# NAVIGATION_-_POWER.net
KiCad netlist of a schematic drawn in Altium Designer
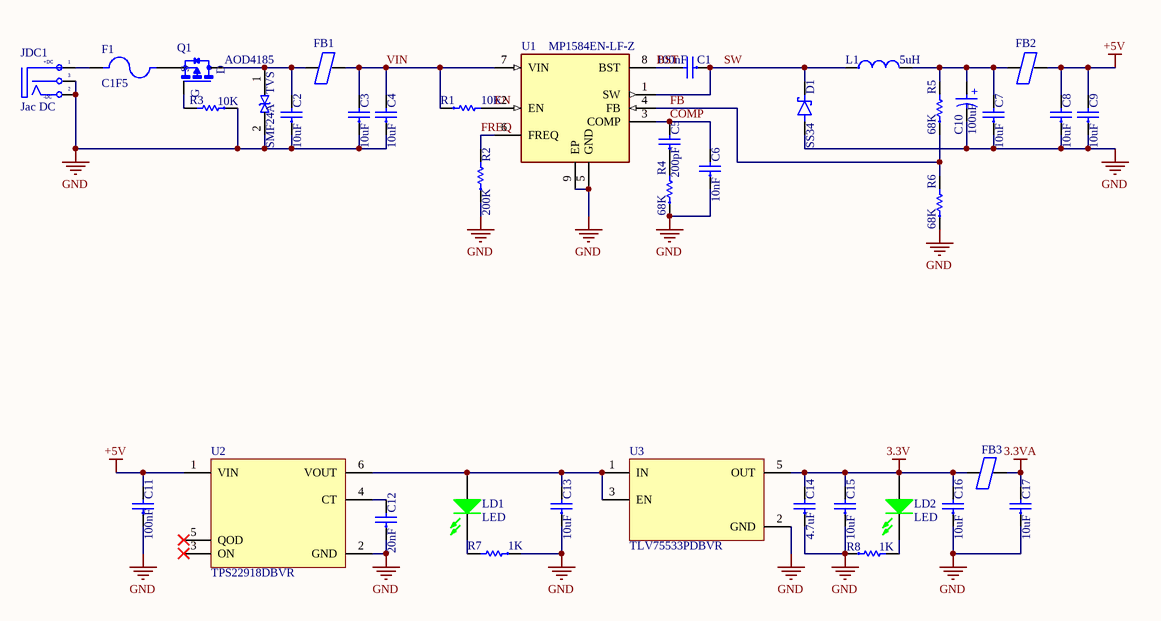
[diagram p0: NAVIGATION - POWER.SchDoc]

(export (version "E")
  (design (tool "Eeschema 10.0.6"))
  (components
    (comp (ref "C1")
      (value "100nF")
      (footprint "CAP-CER0402-0.5H")
      (description "CAP CER 100nF 10% 50V X7R 0402 SMD")
      (libsource (lib "2502-GMQLITE-MAIN") (part "CAPCER0013 100nF 10% 50V X7R 0402 SMD"))
    )
    (comp (ref "C2")
      (value "10uF")
      (footprint "CAP-CER0402-20mil")
      (description "CAP CER 10uF 20% 6.3V X5R 0402 SMD")
      (libsource (lib "2502-GMQLITE-MAIN") (part "CAPCER0040 10uF 20% 6.3V X5R 0402 SMD"))
    )
    (comp (ref "C3")
      (value "10uF")
      (footprint "CAP-CER0402-20mil")
      (description "CAP CER 10uF 20% 6.3V X5R 0402 SMD")
      (libsource (lib "2502-GMQLITE-MAIN") (part "CAPCER0040 10uF 20% 6.3V X5R 0402 SMD"))
    )
    (comp (ref "C4")
      (value "10uF")
      (footprint "CAP-CER0402-20mil")
      (description "CAP CER 10uF 20% 6.3V X5R 0402 SMD")
      (libsource (lib "2502-GMQLITE-MAIN") (part "CAPCER0040 10uF 20% 6.3V X5R 0402 SMD"))
    )
    (comp (ref "C5")
      (value "200pF")
      (footprint "CAP-CER0402-0.5H")
      (description "CAP CER 10nF 10% 25V X7R 0402 SMD")
      (libsource (lib "2502-GMQLITE-MAIN") (part "CAPCER0045 10nF 10% 25V X7R 0402 SMD"))
    )
    (comp (ref "C6")
      (value "10nF")
      (footprint "CAP-CER0402-0.5H")
      (description "CAP CER 10nF 10% 25V X7R 0402 SMD")
      (libsource (lib "2502-GMQLITE-MAIN") (part "CAPCER0045 10nF 10% 25V X7R 0402 SMD"))
    )
    (comp (ref "C7")
      (value "10uF")
      (footprint "CAP-CER0402-20mil")
      (description "CAP CER 10uF 20% 6.3V X5R 0402 SMD")
      (libsource (lib "2502-GMQLITE-MAIN") (part "CAPCER0040 10uF 20% 6.3V X5R 0402 SMD"))
    )
    (comp (ref "C8")
      (value "10uF")
      (footprint "CAP-CER0402-20mil")
      (description "CAP CER 10uF 20% 6.3V X5R 0402 SMD")
      (libsource (lib "2502-GMQLITE-MAIN") (part "CAPCER0040 10uF 20% 6.3V X5R 0402 SMD"))
    )
    (comp (ref "C9")
      (value "10uF")
      (footprint "CAP-CER0402-20mil")
      (description "CAP CER 10uF 20% 6.3V X5R 0402 SMD")
      (libsource (lib "2502-GMQLITE-MAIN") (part "CAPCER0040 10uF 20% 6.3V X5R 0402 SMD"))
    )
    (comp (ref "C10")
      (value "100uF")
      (footprint "Cap Aluminum Lytic 100uF 35V 20%")
      (description "Cap Aluminum Lytic 100uF 35V 20% (6.3 X 7.7mm) SMD 300mA 2000h 105C T/R")
      (fields
        (field (name "MANUFACTURER") "Wurth Electronics")
        (field (name "MANUFACTURER PART NUMBER") "865080545012")
      )
      (libsource (lib "POWER_PIN_CAMERA") (part "Cap Aluminum Lytic 100uF 35V 20%"))
    )
    (comp (ref "C11")
      (value "100nF")
      (footprint "CAP-CER0402-20mil")
      (description "CAP CER 10uF 20% 6.3V X5R 0402 SMD")
      (libsource (lib "2502-GMQLITE-MAIN") (part "CAPCER0040 10uF 20% 6.3V X5R 0402 SMD"))
    )
    (comp (ref "C12")
      (value "20nF")
      (footprint "CAP-CER0402-20mil")
      (description "CAP CER 10uF 20% 6.3V X5R 0402 SMD")
      (libsource (lib "2502-GMQLITE-MAIN") (part "CAPCER0040 10uF 20% 6.3V X5R 0402 SMD"))
    )
    (comp (ref "C13")
      (value "10uF")
      (footprint "CAP-CER0402-20mil")
      (description "CAP CER 10uF 20% 6.3V X5R 0402 SMD")
      (libsource (lib "2502-GMQLITE-MAIN") (part "CAPCER0040 10uF 20% 6.3V X5R 0402 SMD"))
    )
    (comp (ref "C14")
      (value "4.7uF")
      (footprint "CAP-CER0402-20mil")
      (description "CAP CER 10uF 20% 6.3V X5R 0402 SMD")
      (libsource (lib "2502-GMQLITE-MAIN") (part "CAPCER0040 10uF 20% 6.3V X5R 0402 SMD"))
    )
    (comp (ref "C15")
      (value "10uF")
      (footprint "CAP-CER0402-20mil")
      (description "CAP CER 10uF 20% 6.3V X5R 0402 SMD")
      (libsource (lib "2502-GMQLITE-MAIN") (part "CAPCER0040 10uF 20% 6.3V X5R 0402 SMD"))
    )
    (comp (ref "C16")
      (value "10uF")
      (footprint "CAP-CER0402-20mil")
      (description "CAP CER 10uF 20% 6.3V X5R 0402 SMD")
      (libsource (lib "2502-GMQLITE-MAIN") (part "CAPCER0040 10uF 20% 6.3V X5R 0402 SMD"))
    )
    (comp (ref "C17")
      (value "10uF")
      (footprint "CAP-CER0402-20mil")
      (description "CAP CER 10uF 20% 6.3V X5R 0402 SMD")
      (libsource (lib "2502-GMQLITE-MAIN") (part "CAPCER0040 10uF 20% 6.3V X5R 0402 SMD"))
    )
    (comp (ref "D1")
      (value "SS34")
      (footprint "DIO_SS34")
      (description "3A, 40V, Schottky Rectifier")
      (fields (field (name "MF") "Taiwan Semiconductor"))
      (libsource (lib "SS34") (part "SS34"))
    )
    (comp (ref "F1")
      (value "C1F5")
      (footprint "FUSE C1F5")
      (description "Fuse Chip Fast Acting 5A 125V SMD Solder Pad 1206 3.2 X 1.58 X 0.63mm")
      (fields (field (name "MANUFACTURER") "Bel TRP"))
      (libsource (lib "POWER_PIN_CAMERA") (part "C1F5"))
    )
    (comp (ref "FB1")
      (value "100MHz 2A 50mOhm")
      (footprint "FB 0603")
      (description "Ferrite Beads Multi-Layer 120Ohm 25% 100MHz 2A 50mOhm DCR 0603 Paper T/R")
      (fields
        (field (name "MANUFACTURER") "Murata")
        (field (name "MANUFACTURER PART NUMBER") "BLM18PG121SN1D")
      )
      (libsource (lib "POWER_PIN_CAMERA") (part "BLM18PG121SN1D"))
    )
    (comp (ref "FB2")
      (value "100MHz 2A 50mOhm")
      (footprint "FB 0603")
      (description "Ferrite Beads Multi-Layer 120Ohm 25% 100MHz 2A 50mOhm DCR 0603 Paper T/R")
      (fields
        (field (name "MANUFACTURER") "Murata")
        (field (name "MANUFACTURER PART NUMBER") "BLM18PG121SN1D")
      )
      (libsource (lib "POWER_PIN_CAMERA") (part "BLM18PG121SN1D"))
    )
    (comp (ref "FB3")
      (value "100MHz 2A 50mOhm")
      (footprint "FB 0603")
      (description "Ferrite Beads Multi-Layer 120Ohm 25% 100MHz 2A 50mOhm DCR 0603 Paper T/R")
      (fields
        (field (name "MANUFACTURER") "Murata")
        (field (name "MANUFACTURER PART NUMBER") "BLM18PG121SN1D")
      )
      (libsource (lib "POWER_PIN_CAMERA") (part "BLM18PG121SN1D"))
    )
    (comp (ref "JDC1")
      (value "Jac DC")
      (footprint "DC0")
      (description "Jac DC input")
      (libsource (lib "2502-GMQLITE-MAIN") (part "DCIN"))
    )
    (comp (ref "L1")
      (value "5uH")
      (footprint "IND-06030-1uH")
      (description "IND MOI 1W2T 1.5uH 20% 14A 0630 SMD")
      (libsource (lib "2502-GMQLITE-MAIN") (part "INDMOI0013 1W2T 1.5uH 20% 14A 0630 SMD"))
    )
    (comp (ref "LD1")
      (value "LED")
      (footprint "LED-IND0402-GRE-0.4H")
      (description "LED IND GRE CLR 2.4V 20mA 0402 SMD")
      (libsource (lib "2502-GMQLITE-MAIN") (part "LEDIND0005 GRE CLR 2.4V 20mA 0402 SMD"))
    )
    (comp (ref "LD2")
      (value "LED")
      (footprint "LED-IND0402-GRE-0.4H")
      (description "LED IND GRE CLR 2.4V 20mA 0402 SMD")
      (libsource (lib "2502-GMQLITE-MAIN") (part "LEDIND0005 GRE CLR 2.4V 20mA 0402 SMD"))
    )
    (comp (ref "Q1")
      (value "AOD4185")
      (footprint "AOD4185")
      (description "Trans MOSFET P-CH 40V 40A 3-Pin(2+Tab) DPAK")
      (fields (field (name "MANUFACTURER") "Alpha & Omega Semiconductor"))
      (libsource (lib "POWER_PIN_CAMERA") (part "AOD4185"))
    )
    (comp (ref "R1")
      (value "10K")
      (footprint "RES-CHP0402-0.35H")
      (description "RES CHP 10K 1% 1/16W 0402 SMD")
      (libsource (lib "2502-GMQLITE-MAIN") (part "RESCHP0073 10K 1% 0402 SMD"))
    )
    (comp (ref "R2")
      (value "200K")
      (footprint "RES-CHP0402-0.35H")
      (description "RES CHP 100K 1% 1/16W 0402 SMD")
      (libsource (lib "2502-GMQLITE-MAIN") (part "RESCHP0097 100K 1% 0402 SMD"))
    )
    (comp (ref "R3")
      (value "10K")
      (footprint "RES-CHP0402-0.35H")
      (description "RES CHP 100K 1% 1/16W 0402 SMD")
      (libsource (lib "2502-GMQLITE-MAIN") (part "RESCHP0097 100K 1% 0402 SMD"))
    )
    (comp (ref "R4")
      (value "68K")
      (footprint "RES-CHP0402-0.35H")
      (description "RES CHP 100K 1% 1/16W 0402 SMD")
      (libsource (lib "2502-GMQLITE-MAIN") (part "RESCHP0097 100K 1% 0402 SMD"))
    )
    (comp (ref "R5")
      (value "68K")
      (footprint "RES-CHP0402-0.35H")
      (description "RES CHP 100K 1% 1/16W 0402 SMD")
      (libsource (lib "2502-GMQLITE-MAIN") (part "RESCHP0097 100K 1% 0402 SMD"))
    )
    (comp (ref "R6")
      (value "68K")
      (footprint "RES-CHP0402-0.35H")
      (description "RES CHP 100K 1% 1/16W 0402 SMD")
      (libsource (lib "2502-GMQLITE-MAIN") (part "RESCHP0097 100K 1% 0402 SMD"))
    )
    (comp (ref "R7")
      (value "1K")
      (footprint "RES-CHP0402-0.35H")
      (description "RES CHP 100K 1% 1/16W 0402 SMD")
      (libsource (lib "2502-GMQLITE-MAIN") (part "RESCHP0097 100K 1% 0402 SMD"))
    )
    (comp (ref "R8")
      (value "1K")
      (footprint "RES-CHP0402-0.35H")
      (description "RES CHP 100K 1% 1/16W 0402 SMD")
      (libsource (lib "2502-GMQLITE-MAIN") (part "RESCHP0097 100K 1% 0402 SMD"))
    )
    (comp (ref "TVS")
      (value "SMF24A")
      (footprint "TVS24V")
      (description "TVS DIODE 24VWM 38.9VC SOD123F")
      (fields (field (name "MANUFACTURER") "Littelfuse"))
      (libsource (lib "POWER_PIN_CAMERA") (part "SMF24A"))
    )
    (comp (ref "U1")
      (value "MP1584EN-LF-Z")
      (footprint "SOIC127P600X170-9N")
      (fields (field (name "MF") "Monolithic Power Systems") (field (name "MP") "MP1584ENLFZ"))
      (libsource (lib "MP1584EN-LF-Z") (part "MP1584EN-LF-Z"))
    )
    (comp (ref "U2")
      (value "TPS22918DBVR")
      (footprint "SOT95P280X145-6N")
      (description "5.5-V, 2-A, 52-mÎ© load switch with adj. rise time and adj. output discharge")
      (fields (field (name "MF") "Texas Instruments"))
      (libsource (lib "TPS22918DBVR") (part "TPS22918DBVR"))
    )
    (comp (ref "U3")
      (value "TLV75533PDBVR")
      (footprint "SOT95P280X145-5N")
      (description "500-mA High-PSRR Low-IQ-Tief-Dropout-Spannungsregler mitablem")
      (fields (field (name "MF") "Texas Instruments"))
      (libsource (lib "TLV75533PDBVR") (part "TLV75533PDBVR"))
    )
  )
  (nets
    (net (code "1") (name "+5V") (class "Default")
      (node (ref "C11") (pin "2") (pinfunction "2_2") (pintype "passive"))
      (node (ref "C8") (pin "2") (pinfunction "2_2") (pintype "passive"))
      (node (ref "C9") (pin "2") (pinfunction "2_2") (pintype "passive"))
      (node (ref "FB2") (pin "2") (pinfunction "2_2") (pintype "passive"))
      (node (ref "U2") (pin "1") (pinfunction "VIN_1") (pintype "passive"))
    )
    (net (code "2") (name "/BST") (class "Default")
      (node (ref "C1") (pin "2") (pinfunction "2_2") (pintype "passive"))
      (node (ref "U1") (pin "8") (pinfunction "BST_8") (pintype "passive"))
    )
    (net (code "3") (name "/COMP") (class "Default")
      (node (ref "C5") (pin "2") (pinfunction "2_2") (pintype "passive"))
      (node (ref "C6") (pin "2") (pinfunction "2_2") (pintype "passive"))
      (node (ref "U1") (pin "3") (pinfunction "COMP_3") (pintype "passive"))
    )
    (net (code "4") (name "/EN") (class "Default")
      (node (ref "R1") (pin "2") (pinfunction "2_2") (pintype "passive"))
      (node (ref "U1") (pin "2") (pinfunction "EN_2") (pintype "input"))
    )
    (net (code "5") (name "/FB") (class "Default")
      (node (ref "R5") (pin "1") (pinfunction "1_1") (pintype "passive"))
      (node (ref "R6") (pin "2") (pinfunction "2_2") (pintype "passive"))
      (node (ref "U1") (pin "4") (pinfunction "FB_4") (pintype "input"))
    )
    (net (code "6") (name "/FREQ") (class "Default")
      (node (ref "R2") (pin "2") (pinfunction "2_2") (pintype "passive"))
      (node (ref "U1") (pin "6") (pinfunction "FREQ_6") (pintype "passive"))
    )
    (net (code "7") (name "/SW") (class "Default")
      (node (ref "C1") (pin "1") (pinfunction "1_1") (pintype "passive"))
      (node (ref "D1") (pin "C") (pinfunction "K_C") (pintype "passive"))
      (node (ref "L1") (pin "1") (pinfunction "1_1") (pintype "passive"))
      (node (ref "U1") (pin "1") (pinfunction "SW_1") (pintype "output"))
    )
    (net (code "8") (name "/VIN") (class "Default")
      (node (ref "C3") (pin "2") (pinfunction "2_2") (pintype "passive"))
      (node (ref "C4") (pin "2") (pinfunction "2_2") (pintype "passive"))
      (node (ref "FB1") (pin "2") (pinfunction "2_2") (pintype "passive"))
      (node (ref "R1") (pin "1") (pinfunction "1_1") (pintype "passive"))
      (node (ref "U1") (pin "7") (pinfunction "VIN_7") (pintype "input"))
    )
    (net (code "9") (name "3.3V") (class "Default")
      (node (ref "C14") (pin "2") (pinfunction "2_2") (pintype "passive"))
      (node (ref "C15") (pin "2") (pinfunction "2_2") (pintype "passive"))
      (node (ref "C16") (pin "2") (pinfunction "2_2") (pintype "passive"))
      (node (ref "FB3") (pin "1") (pinfunction "1_1") (pintype "passive"))
      (node (ref "LD2") (pin "1") (pinfunction "A_1") (pintype "passive"))
      (node (ref "U3") (pin "5") (pinfunction "OUT_5") (pintype "passive"))
    )
    (net (code "10") (name "3.3VA") (class "Default")
      (node (ref "C17") (pin "2") (pinfunction "2_2") (pintype "passive"))
      (node (ref "FB3") (pin "2") (pinfunction "2_2") (pintype "passive"))
    )
    (net (code "11") (name "GND") (class "Default")
      (node (ref "C10") (pin "2") (pinfunction "N_2") (pintype "passive"))
      (node (ref "C11") (pin "1") (pinfunction "1_1") (pintype "passive"))
      (node (ref "C12") (pin "1") (pinfunction "1_1") (pintype "passive"))
      (node (ref "C13") (pin "1") (pinfunction "1_1") (pintype "passive"))
      (node (ref "C14") (pin "1") (pinfunction "1_1") (pintype "passive"))
      (node (ref "C15") (pin "1") (pinfunction "1_1") (pintype "passive"))
      (node (ref "C16") (pin "1") (pinfunction "1_1") (pintype "passive"))
      (node (ref "C17") (pin "1") (pinfunction "1_1") (pintype "passive"))
      (node (ref "C2") (pin "1") (pinfunction "1_1") (pintype "passive"))
      (node (ref "C3") (pin "1") (pinfunction "1_1") (pintype "passive"))
      (node (ref "C4") (pin "1") (pinfunction "1_1") (pintype "passive"))
      (node (ref "C6") (pin "1") (pinfunction "1_1") (pintype "passive"))
      (node (ref "C7") (pin "1") (pinfunction "1_1") (pintype "passive"))
      (node (ref "C8") (pin "1") (pinfunction "1_1") (pintype "passive"))
      (node (ref "C9") (pin "1") (pinfunction "1_1") (pintype "passive"))
      (node (ref "D1") (pin "A") (pinfunction "A_A") (pintype "passive"))
      (node (ref "JDC1") (pin "2") (pinfunction "TN_2") (pintype "passive"))
      (node (ref "JDC1") (pin "3") (pinfunction "S_3") (pintype "power_in"))
      (node (ref "R2") (pin "1") (pinfunction "1_1") (pintype "passive"))
      (node (ref "R3") (pin "1") (pinfunction "1_1") (pintype "passive"))
      (node (ref "R4") (pin "1") (pinfunction "1_1") (pintype "passive"))
      (node (ref "R6") (pin "1") (pinfunction "1_1") (pintype "passive"))
      (node (ref "R7") (pin "1") (pinfunction "1_1") (pintype "passive"))
      (node (ref "R8") (pin "1") (pinfunction "1_1") (pintype "passive"))
      (node (ref "TVS") (pin "2") (pinfunction "2_2") (pintype "passive"))
      (node (ref "U1") (pin "5") (pinfunction "GND_5") (pintype "power_in"))
      (node (ref "U1") (pin "9") (pinfunction "EP_9") (pintype "power_in"))
      (node (ref "U2") (pin "2") (pinfunction "GND_2") (pintype "passive"))
      (node (ref "U3") (pin "2") (pinfunction "GND_2") (pintype "passive"))
    )
    (net (code "12") (name "Net-(C5-Pad1)") (class "Default")
      (node (ref "C5") (pin "1") (pinfunction "1_1") (pintype "passive"))
      (node (ref "R4") (pin "2") (pinfunction "2_2") (pintype "passive"))
    )
    (net (code "13") (name "Net-(C10-P)") (class "Default")
      (node (ref "C10") (pin "1") (pinfunction "P_1") (pintype "passive"))
      (node (ref "C7") (pin "2") (pinfunction "2_2") (pintype "passive"))
      (node (ref "FB2") (pin "1") (pinfunction "1_1") (pintype "passive"))
      (node (ref "L1") (pin "2") (pinfunction "2_2") (pintype "passive"))
      (node (ref "R5") (pin "2") (pinfunction "2_2") (pintype "passive"))
    )
    (net (code "14") (name "Net-(JDC1-T)") (class "Default")
      (node (ref "F1") (pin "1") (pinfunction "1_1") (pintype "passive"))
      (node (ref "JDC1") (pin "1") (pinfunction "T_1") (pintype "passive"))
    )
    (net (code "15") (name "Net-(LD1-A)") (class "Default")
      (node (ref "C13") (pin "2") (pinfunction "2_2") (pintype "passive"))
      (node (ref "LD1") (pin "1") (pinfunction "A_1") (pintype "passive"))
      (node (ref "U2") (pin "6") (pinfunction "VOUT_6") (pintype "passive"))
      (node (ref "U3") (pin "1") (pinfunction "IN_1") (pintype "passive"))
      (node (ref "U3") (pin "3") (pinfunction "EN_3") (pintype "passive"))
    )
    (net (code "16") (name "Net-(LD1-K)") (class "Default")
      (node (ref "LD1") (pin "2") (pinfunction "K_2") (pintype "passive"))
      (node (ref "R7") (pin "2") (pinfunction "2_2") (pintype "passive"))
    )
    (net (code "17") (name "Net-(LD2-K)") (class "Default")
      (node (ref "LD2") (pin "2") (pinfunction "K_2") (pintype "passive"))
      (node (ref "R8") (pin "2") (pinfunction "2_2") (pintype "passive"))
    )
    (net (code "18") (name "Net-(Q1-D)") (class "Default")
      (node (ref "C2") (pin "2") (pinfunction "2_2") (pintype "passive"))
      (node (ref "FB1") (pin "1") (pinfunction "1_1") (pintype "passive"))
      (node (ref "Q1") (pin "4") (pinfunction "D_4") (pintype "passive"))
      (node (ref "TVS") (pin "1") (pinfunction "1_1") (pintype "passive"))
    )
    (net (code "19") (name "Net-(Q1-G)") (class "Default")
      (node (ref "Q1") (pin "1") (pinfunction "G_1") (pintype "passive"))
      (node (ref "R3") (pin "2") (pinfunction "2_2") (pintype "passive"))
    )
    (net (code "20") (name "Net-(Q1-S)") (class "Default")
      (node (ref "F1") (pin "2") (pinfunction "2_2") (pintype "passive"))
      (node (ref "Q1") (pin "3") (pinfunction "S_3") (pintype "passive"))
    )
    (net (code "21") (name "Net-(U2-CT)") (class "Default")
      (node (ref "C12") (pin "2") (pinfunction "2_2") (pintype "passive"))
      (node (ref "U2") (pin "4") (pinfunction "CT_4") (pintype "passive"))
    )
    (net (code "22") (name "unconnected-(U2-ON-Pad3)") (class "Default")
      (node (ref "U2") (pin "3") (pinfunction "ON_3") (pintype "passive+no_connect"))
    )
    (net (code "23") (name "unconnected-(U2-QOD-Pad5)") (class "Default")
      (node (ref "U2") (pin "5") (pinfunction "QOD_5") (pintype "passive+no_connect"))
    )
  )
)
